# MCU20.net
KiCad netlist of a schematic drawn in Altium Designer
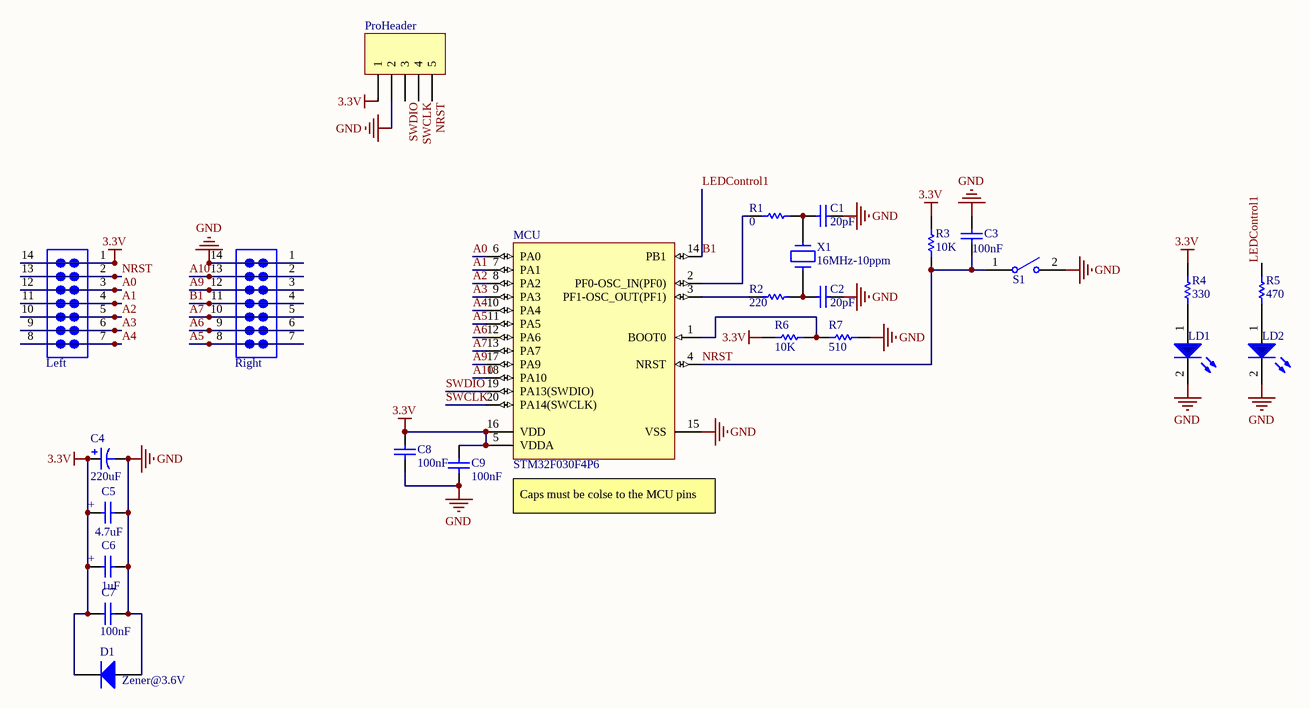
[diagram p0: MCU20.SchDoc]

(export (version "E")
  (design (tool "Eeschema 10.0.6"))
  (components
    (comp (ref "C1")
      (value "20pF")
      (footprint "SMD 805 CAP")
      (libsource (lib "Aryalib") (part "CAP without Pole"))
    )
    (comp (ref "C2")
      (value "20pF")
      (footprint "SMD 805 CAP")
      (libsource (lib "Aryalib") (part "CAP without Pole"))
    )
    (comp (ref "C3")
      (value "100nF")
      (footprint "SMD 805 CAP")
      (libsource (lib "Aryalib") (part "CAP without Pole"))
    )
    (comp (ref "C4") (value "220uF") (footprint "Cap D") (libsource (lib "Aryalib") (part "CAP")))
    (comp (ref "C5")
      (value "4.7uF")
      (footprint "MY_CAP_SMD-A")
      (description "3.2X1.6MM")
      (libsource (lib "AMINLIB") (part "CAP_TANTAL_A"))
    )
    (comp (ref "C6")
      (value "1uF")
      (footprint "MY_CAP_SMD-A")
      (description "3.2X1.6MM")
      (libsource (lib "AMINLIB") (part "CAP_TANTAL_A"))
    )
    (comp (ref "C7")
      (value "100nF")
      (footprint "SMD 805 CAP")
      (libsource (lib "Aryalib") (part "CAP without Pole"))
    )
    (comp (ref "C8")
      (value "100nF")
      (footprint "SMD 805 CAP")
      (libsource (lib "Aryalib") (part "CAP without Pole"))
    )
    (comp (ref "C9")
      (value "100nF")
      (footprint "SMD 805 CAP")
      (libsource (lib "Aryalib") (part "CAP without Pole"))
    )
    (comp (ref "D1")
      (value "Zener@3.6V")
      (footprint "MiniMelf")
      (libsource (lib "Aryalib") (part "Diode 1N4007"))
    )
    (comp (ref "LD1")
      (value "150080BS75000")
      (footprint "LED_0805_Blue")
      (description "SMD mono-color Chip LED, WL-SMCW, Blue")
      (fields
        (field (name "MANUFACTURER") "W黵th Elektronik eiSos GmbH")
        (field (name "CREATED BY") "Christin Otto")
      )
      (libsource (lib "WL-SMCW_rev15b2") (part "WL-SMCW 0805  150080BS75000"))
    )
    (comp (ref "LD2")
      (value "150080BS75000")
      (footprint "LED_0805_Blue")
      (description "SMD mono-color Chip LED, WL-SMCW, Blue")
      (fields
        (field (name "MANUFACTURER") "W黵th Elektronik eiSos GmbH")
        (field (name "CREATED BY") "Christin Otto")
      )
      (libsource (lib "WL-SMCW_rev15b2") (part "WL-SMCW 0805  150080BS75000"))
    )
    (comp (ref "Left")
      (value "WE-2.54 mm Pin Header & Jumper 61301421121")
      (footprint "61301421121")
      (description "WR-PHD 2.54 mm Dual Pin Header")
      (fields
        (field (name "MANUFACTURER") "Würth Elektronik eiSos GmbH")
        (field (name "PARTNO") "61301421121")
        (field (name "CREATED BY") "Karrer Zheng")
      )
      (libsource (lib "WE_WR-PHD_Pin Header_2.54mm_rev15c") (part "WE-2.54 mm Pin Header & Jumper 61301421121"))
    )
    (comp (ref "MCU")
      (value "STM32F030F4P6")
      (footprint "STM-TSSOP20_L")
      (libsource (lib "STMicroelectronics STM32 F0") (part "STM32F030F4P6"))
    )
    (comp (ref "ProHeader")
      (value "WE-2.54 mm Pin Header & Jumper 61300511021")
      (footprint "61300511021")
      (description "WR-PHD 2.54mm Angled Pin Header")
      (fields
        (field (name "MANUFACTURER") "Würth Elektronik eiSos GmbH")
        (field (name "PARTNO") "61300511021")
        (field (name "CREATED BY") "Karrer Zheng")
      )
      (libsource (lib "WE_WR-PHD_Pin Header_2.54mm_rev15c") (part "WE-2.54 mm Pin Header & Jumper 61300511021"))
    )
    (comp (ref "R1") (value "0") (footprint "SMD 805") (libsource (lib "Aryalib") (part "Resistor")))
    (comp (ref "R2") (value "220") (footprint "SMD 805") (libsource (lib "Aryalib") (part "Resistor")))
    (comp (ref "R3") (value "10K") (footprint "SMD 805") (libsource (lib "Aryalib") (part "Resistor")))
    (comp (ref "R4") (value "330") (footprint "SMD 805") (libsource (lib "Aryalib") (part "Resistor")))
    (comp (ref "R5") (value "470") (footprint "SMD 805") (libsource (lib "Aryalib") (part "Resistor")))
    (comp (ref "R6") (value "10K") (footprint "SMD 805") (libsource (lib "Aryalib") (part "Resistor")))
    (comp (ref "R7") (value "510") (footprint "SMD 805") (libsource (lib "Aryalib") (part "Resistor")))
    (comp (ref "Right")
      (value "WE-2.54 mm Pin Header & Jumper 61301421121")
      (footprint "61301421121")
      (description "WR-PHD 2.54 mm Dual Pin Header")
      (fields
        (field (name "MANUFACTURER") "Würth Elektronik eiSos GmbH")
        (field (name "PARTNO") "61301421121")
        (field (name "CREATED BY") "Karrer Zheng")
      )
      (libsource (lib "WE_WR-PHD_Pin Header_2.54mm_rev15c") (part "WE-2.54 mm Pin Header & Jumper 61301421121"))
    )
    (comp (ref "S1")
      (value "Tact Switch")
      (footprint "4341x10438x6")
      (description "WS-TASV 6.0x3.5 mm SMD")
      (fields
        (field (name "PARTNO") "434111043826")
        (field (name "MANUFACTURER") "Wurth Elektronik")
        (field (name "CREATED BY") "Baojun Chen")
      )
      (libsource (lib "WS-TASV_rev15a") (part "WS-TASV, 434111043826"))
    )
    (comp (ref "X1")
      (value "16MHz-10ppm")
      (footprint "My_Crystal")
      (description "Crystal")
      (libsource (lib "AMINLIB") (part "CRYSTAL"))
    )
  )
  (nets
    (net (code "1") (name "/A0") (class "Default")
      (node (ref "Left") (pin "12") (pinfunction "12_12") (pintype "passive"))
      (node (ref "Left") (pin "3") (pinfunction "3_3") (pintype "passive"))
      (node (ref "MCU") (pin "6") (pinfunction "PA0_6") (pintype "bidirectional"))
    )
    (net (code "2") (name "/A1") (class "Default")
      (node (ref "Left") (pin "11") (pinfunction "11_11") (pintype "passive"))
      (node (ref "Left") (pin "4") (pinfunction "4_4") (pintype "passive"))
      (node (ref "MCU") (pin "7") (pinfunction "PA1_7") (pintype "bidirectional"))
    )
    (net (code "3") (name "/A2") (class "Default")
      (node (ref "Left") (pin "10") (pinfunction "10_10") (pintype "passive"))
      (node (ref "Left") (pin "5") (pinfunction "5_5") (pintype "passive"))
      (node (ref "MCU") (pin "8") (pinfunction "PA2_8") (pintype "bidirectional"))
    )
    (net (code "4") (name "/A3") (class "Default")
      (node (ref "Left") (pin "6") (pinfunction "6_6") (pintype "passive"))
      (node (ref "Left") (pin "9") (pinfunction "9_9") (pintype "passive"))
      (node (ref "MCU") (pin "9") (pinfunction "PA3_9") (pintype "bidirectional"))
    )
    (net (code "5") (name "/A4") (class "Default")
      (node (ref "Left") (pin "7") (pinfunction "7_7") (pintype "passive"))
      (node (ref "Left") (pin "8") (pinfunction "8_8") (pintype "passive"))
      (node (ref "MCU") (pin "10") (pinfunction "PA4_10") (pintype "bidirectional"))
    )
    (net (code "6") (name "/A5") (class "Default")
      (node (ref "MCU") (pin "11") (pinfunction "PA5_11") (pintype "bidirectional"))
      (node (ref "Right") (pin "7") (pinfunction "7_7") (pintype "passive"))
      (node (ref "Right") (pin "8") (pinfunction "8_8") (pintype "passive"))
    )
    (net (code "7") (name "/A6") (class "Default")
      (node (ref "MCU") (pin "12") (pinfunction "PA6_12") (pintype "bidirectional"))
      (node (ref "Right") (pin "6") (pinfunction "6_6") (pintype "passive"))
      (node (ref "Right") (pin "9") (pinfunction "9_9") (pintype "passive"))
    )
    (net (code "8") (name "/A7") (class "Default")
      (node (ref "MCU") (pin "13") (pinfunction "PA7_13") (pintype "bidirectional"))
      (node (ref "Right") (pin "10") (pinfunction "10_10") (pintype "passive"))
      (node (ref "Right") (pin "5") (pinfunction "5_5") (pintype "passive"))
    )
    (net (code "9") (name "/A9") (class "Default")
      (node (ref "MCU") (pin "17") (pinfunction "PA9_17") (pintype "bidirectional"))
      (node (ref "Right") (pin "12") (pinfunction "12_12") (pintype "passive"))
      (node (ref "Right") (pin "3") (pinfunction "3_3") (pintype "passive"))
    )
    (net (code "10") (name "/A10") (class "Default")
      (node (ref "MCU") (pin "18") (pinfunction "PA10_18") (pintype "bidirectional"))
      (node (ref "Right") (pin "13") (pinfunction "13_13") (pintype "passive"))
      (node (ref "Right") (pin "2") (pinfunction "2_2") (pintype "passive"))
    )
    (net (code "11") (name "/B1") (class "Default")
      (node (ref "MCU") (pin "14") (pinfunction "PB1_14") (pintype "bidirectional"))
      (node (ref "R5") (pin "2") (pinfunction "2_2") (pintype "passive"))
      (node (ref "Right") (pin "11") (pinfunction "11_11") (pintype "passive"))
      (node (ref "Right") (pin "4") (pinfunction "4_4") (pintype "passive"))
    )
    (net (code "12") (name "/NRST") (class "Default")
      (node (ref "C3") (pin "1") (pinfunction "1_1") (pintype "passive"))
      (node (ref "Left") (pin "13") (pinfunction "13_13") (pintype "passive"))
      (node (ref "Left") (pin "2") (pinfunction "2_2") (pintype "passive"))
      (node (ref "MCU") (pin "4") (pinfunction "NRST_4") (pintype "bidirectional"))
      (node (ref "ProHeader") (pin "5") (pinfunction "5_5") (pintype "passive"))
      (node (ref "R3") (pin "1") (pinfunction "1_1") (pintype "passive"))
      (node (ref "S1") (pin "1") (pinfunction "1_1") (pintype "passive"))
    )
    (net (code "13") (name "/SWCLK") (class "Default")
      (node (ref "MCU") (pin "20") (pinfunction "PA14(SWCLK)_20") (pintype "bidirectional"))
      (node (ref "ProHeader") (pin "4") (pinfunction "4_4") (pintype "passive"))
    )
    (net (code "14") (name "/SWDIO") (class "Default")
      (node (ref "MCU") (pin "19") (pinfunction "PA13(SWDIO)_19") (pintype "bidirectional"))
      (node (ref "ProHeader") (pin "3") (pinfunction "3_3") (pintype "passive"))
    )
    (net (code "15") (name "3.3V") (class "Default")
      (node (ref "C4") (pin "1") (pinfunction "1_1") (pintype "passive"))
      (node (ref "C5") (pin "+") (pinfunction "+_+") (pintype "passive"))
      (node (ref "C6") (pin "+") (pinfunction "+_+") (pintype "passive"))
      (node (ref "C7") (pin "1") (pinfunction "1_1") (pintype "passive"))
      (node (ref "C8") (pin "1") (pinfunction "1_1") (pintype "passive"))
      (node (ref "C9") (pin "1") (pinfunction "1_1") (pintype "passive"))
      (node (ref "D1") (pin "2") (pinfunction "2_2") (pintype "passive"))
      (node (ref "Left") (pin "1") (pinfunction "1_1") (pintype "passive"))
      (node (ref "Left") (pin "14") (pinfunction "14_14") (pintype "passive"))
      (node (ref "MCU") (pin "16") (pinfunction "VDD_16") (pintype "power_in"))
      (node (ref "MCU") (pin "5") (pinfunction "VDDA_5") (pintype "power_in"))
      (node (ref "ProHeader") (pin "1") (pinfunction "1_1") (pintype "passive"))
      (node (ref "R3") (pin "2") (pinfunction "2_2") (pintype "passive"))
      (node (ref "R4") (pin "2") (pinfunction "2_2") (pintype "passive"))
      (node (ref "R6") (pin "2") (pinfunction "2_2") (pintype "passive"))
    )
    (net (code "16") (name "GND") (class "Default")
      (node (ref "C1") (pin "1") (pinfunction "1_1") (pintype "passive"))
      (node (ref "C2") (pin "2") (pinfunction "2_2") (pintype "passive"))
      (node (ref "C3") (pin "2") (pinfunction "2_2") (pintype "passive"))
      (node (ref "C4") (pin "2") (pinfunction "2_2") (pintype "passive"))
      (node (ref "C5") (pin "-") (pinfunction "-_-") (pintype "passive"))
      (node (ref "C6") (pin "-") (pinfunction "-_-") (pintype "passive"))
      (node (ref "C7") (pin "2") (pinfunction "2_2") (pintype "passive"))
      (node (ref "C8") (pin "2") (pinfunction "2_2") (pintype "passive"))
      (node (ref "C9") (pin "2") (pinfunction "2_2") (pintype "passive"))
      (node (ref "D1") (pin "1") (pinfunction "1_1") (pintype "passive"))
      (node (ref "LD1") (pin "2") (pinfunction "C_2") (pintype "passive"))
      (node (ref "LD2") (pin "2") (pinfunction "C_2") (pintype "passive"))
      (node (ref "MCU") (pin "15") (pinfunction "VSS_15") (pintype "power_in"))
      (node (ref "ProHeader") (pin "2") (pinfunction "2_2") (pintype "passive"))
      (node (ref "R7") (pin "1") (pinfunction "1_1") (pintype "passive"))
      (node (ref "Right") (pin "1") (pinfunction "1_1") (pintype "passive"))
      (node (ref "Right") (pin "14") (pinfunction "14_14") (pintype "passive"))
      (node (ref "S1") (pin "2") (pinfunction "2_2") (pintype "passive"))
    )
    (net (code "17") (name "Net-(C1-Pad2)") (class "Default")
      (node (ref "C1") (pin "2") (pinfunction "2_2") (pintype "passive"))
      (node (ref "R1") (pin "2") (pinfunction "2_2") (pintype "passive"))
      (node (ref "X1") (pin "2") (pinfunction "2_2") (pintype "passive"))
    )
    (net (code "18") (name "Net-(C2-Pad1)") (class "Default")
      (node (ref "C2") (pin "1") (pinfunction "1_1") (pintype "passive"))
      (node (ref "R2") (pin "2") (pinfunction "2_2") (pintype "passive"))
      (node (ref "X1") (pin "1") (pinfunction "1_1") (pintype "passive"))
    )
    (net (code "19") (name "Net-(LD1-A)") (class "Default")
      (node (ref "LD1") (pin "1") (pinfunction "A_1") (pintype "passive"))
      (node (ref "R4") (pin "1") (pinfunction "1_1") (pintype "passive"))
    )
    (net (code "20") (name "Net-(LD2-A)") (class "Default")
      (node (ref "LD2") (pin "1") (pinfunction "A_1") (pintype "passive"))
      (node (ref "R5") (pin "1") (pinfunction "1_1") (pintype "passive"))
    )
    (net (code "21") (name "Net-(MCU-BOOT0)") (class "Default")
      (node (ref "MCU") (pin "1") (pinfunction "BOOT0_1") (pintype "input"))
      (node (ref "R6") (pin "1") (pinfunction "1_1") (pintype "passive"))
      (node (ref "R7") (pin "2") (pinfunction "2_2") (pintype "passive"))
    )
    (net (code "22") (name "Net-(MCU-PF0-OSC_IN(PF0))") (class "Default")
      (node (ref "MCU") (pin "2") (pinfunction "PF0-OSC_IN(PF0)_2") (pintype "bidirectional"))
      (node (ref "R1") (pin "1") (pinfunction "1_1") (pintype "passive"))
    )
    (net (code "23") (name "Net-(MCU-PF1-OSC_OUT(PF1))") (class "Default")
      (node (ref "MCU") (pin "3") (pinfunction "PF1-OSC_OUT(PF1)_3") (pintype "bidirectional"))
      (node (ref "R2") (pin "1") (pinfunction "1_1") (pintype "passive"))
    )
  )
)
